# ui_cpu_power.net
KiCad netlist of a schematic drawn in Altium Designer
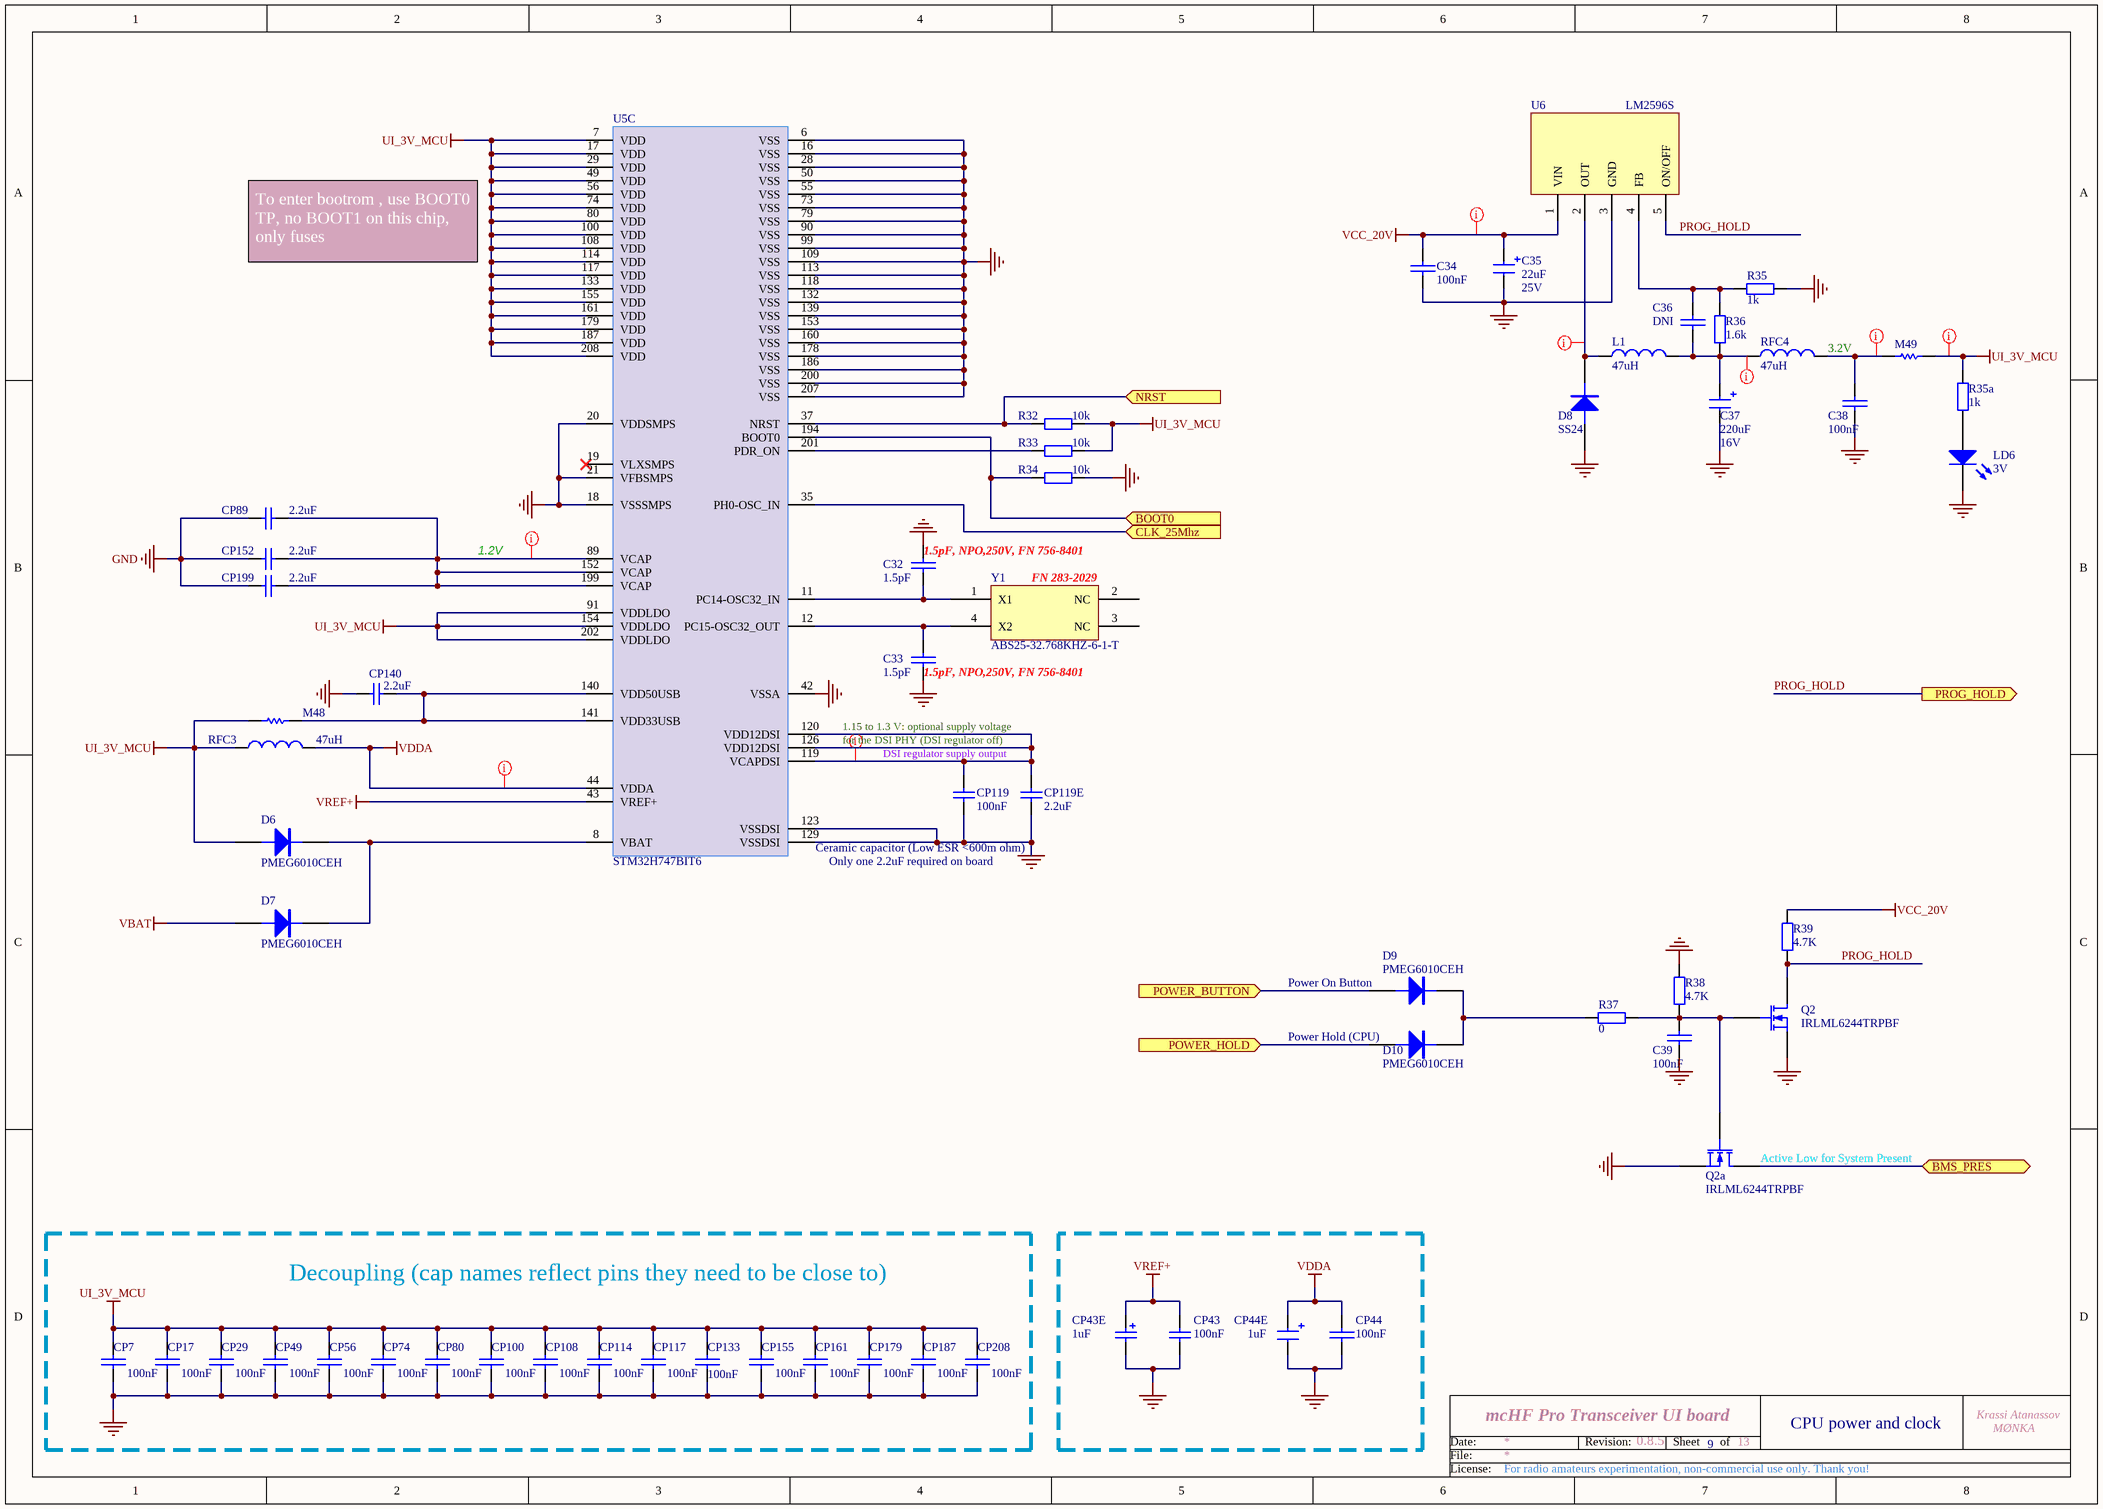
[diagram p0: ui_cpu_power.SchDoc]

(export (version "E")
  (design (tool "Eeschema 10.0.6"))
  (components
    (comp (ref "C32")
      (value "1.5pF")
      (footprint "0805")
      (description "Capacitor")
      (libsource (lib "mcHF_ui") (part "CAP"))
    )
    (comp (ref "C33")
      (value "1.5pF")
      (footprint "0805")
      (description "Capacitor")
      (libsource (lib "mcHF_ui") (part "CAP"))
    )
    (comp (ref "C34")
      (value "100nF")
      (footprint "0805")
      (description "Capacitor")
      (fields (field (name "VOLTAGE") "100V"))
      (libsource (lib "mcHF_rf") (part "CAP"))
    )
    (comp (ref "C35")
      (value "22uF")
      (footprint "1206_Elec_Cap")
      (description "Electrolitic capacitor")
      (fields (field (name "VOLTAGE") "25V"))
      (libsource (lib "mcHF_rf") (part "CAP-POL"))
    )
    (comp (ref "C36")
      (value "DNI")
      (footprint "0805")
      (description "Capacitor")
      (fields (field (name "VOLTAGE") "100V"))
      (libsource (lib "mcHF_rf") (part "CAP"))
    )
    (comp (ref "C37")
      (value "220uF")
      (footprint "CAP_ALUM_Pro")
      (description "Electrolitic capacitor")
      (fields (field (name "VOLTAGE") "16V"))
      (libsource (lib "mcHF_rf") (part "CAP-POL"))
    )
    (comp (ref "C38")
      (value "100nF")
      (footprint "0805")
      (description "Capacitor")
      (fields (field (name "VOLTAGE") "100V"))
      (libsource (lib "mcHF_rf") (part "CAP"))
    )
    (comp (ref "C39")
      (value "100nF")
      (footprint "0805")
      (description "Capacitor")
      (fields (field (name "VOLTAGE") "100V"))
      (libsource (lib "mcHF_rf") (part "CAP"))
    )
    (comp (ref "CP7")
      (value "100nF")
      (footprint "0805")
      (description "Capacitor")
      (libsource (lib "mcHF_ui") (part "CAP"))
    )
    (comp (ref "CP17")
      (value "100nF")
      (footprint "0805")
      (description "Capacitor")
      (libsource (lib "mcHF_ui") (part "CAP"))
    )
    (comp (ref "CP29")
      (value "100nF")
      (footprint "0805")
      (description "Capacitor")
      (libsource (lib "mcHF_ui") (part "CAP"))
    )
    (comp (ref "CP43")
      (value "100nF")
      (footprint "0805")
      (description "Capacitor")
      (fields (field (name "PUBLISHER") "Altium Limited"))
      (libsource (lib "Miscellaneous Devices") (part "Cap"))
    )
    (comp (ref "CP43E")
      (value "1uF")
      (footprint "1206_Elec_Cap")
      (fields (field (name "PUBLISHER") "Altium Limited"))
      (libsource (lib "Miscellaneous Devices") (part "Cap Pol1"))
    )
    (comp (ref "CP44")
      (value "100nF")
      (footprint "0805")
      (description "Capacitor")
      (libsource (lib "mcHF_ui") (part "CAP"))
    )
    (comp (ref "CP44E")
      (value "1uF")
      (footprint "1206_Elec_Cap")
      (description "Electrolitic capacitor")
      (libsource (lib "mcHF_ui") (part "CAP-POL"))
    )
    (comp (ref "CP49")
      (value "100nF")
      (footprint "0805")
      (description "Capacitor")
      (libsource (lib "mcHF_ui") (part "CAP"))
    )
    (comp (ref "CP56")
      (value "100nF")
      (footprint "0805")
      (description "Capacitor")
      (libsource (lib "mcHF_ui") (part "CAP"))
    )
    (comp (ref "CP74")
      (value "100nF")
      (footprint "0805")
      (description "Capacitor")
      (libsource (lib "mcHF_ui") (part "CAP"))
    )
    (comp (ref "CP80")
      (value "100nF")
      (footprint "0805")
      (description "Capacitor")
      (libsource (lib "mcHF_ui") (part "CAP"))
    )
    (comp (ref "CP89")
      (value "2.2uF")
      (footprint "0805")
      (description "Capacitor")
      (fields (field (name "PUBLISHER") "Altium Limited"))
      (libsource (lib "Miscellaneous Devices") (part "cap"))
    )
    (comp (ref "CP100")
      (value "100nF")
      (footprint "0805")
      (description "Capacitor")
      (libsource (lib "mcHF_ui") (part "CAP"))
    )
    (comp (ref "CP108")
      (value "100nF")
      (footprint "0805")
      (description "Capacitor")
      (libsource (lib "mcHF_ui") (part "CAP"))
    )
    (comp (ref "CP114")
      (value "100nF")
      (footprint "0805")
      (description "Capacitor")
      (libsource (lib "mcHF_ui") (part "CAP"))
    )
    (comp (ref "CP117")
      (value "100nF")
      (footprint "0805")
      (description "Capacitor")
      (libsource (lib "mcHF_ui") (part "CAP"))
    )
    (comp (ref "CP119")
      (value "100nF")
      (footprint "0805")
      (description "Capacitor")
      (fields (field (name "PUBLISHER") "Altium Limited"))
      (libsource (lib "Miscellaneous Devices") (part "CAP"))
    )
    (comp (ref "CP119E")
      (value "2.2uF")
      (footprint "0805")
      (description "Capacitor")
      (fields (field (name "PUBLISHER") "Altium Limited"))
      (libsource (lib "Miscellaneous Devices") (part "CAP"))
    )
    (comp (ref "CP133")
      (value "100nF")
      (footprint "0805")
      (description "Capacitor")
      (libsource (lib "mcHF_ui") (part "CAP"))
    )
    (comp (ref "CP140")
      (value "2.2uF")
      (footprint "0805")
      (description "0603  X5R 1礔")
      (fields (field (name "TOLERANCE") "10%"))
      (libsource (lib "MB963_1") (part "CAP SMD 0603  X5R 1礔 25V 10%"))
    )
    (comp (ref "CP152")
      (value "2.2uF")
      (footprint "0805")
      (description "Capacitor")
      (fields (field (name "PUBLISHER") "Altium Limited"))
      (libsource (lib "Miscellaneous Devices") (part "cap"))
    )
    (comp (ref "CP155")
      (value "100nF")
      (footprint "0805")
      (description "Capacitor")
      (libsource (lib "mcHF_ui") (part "CAP"))
    )
    (comp (ref "CP161")
      (value "100nF")
      (footprint "0805")
      (description "Capacitor")
      (libsource (lib "mcHF_ui") (part "CAP"))
    )
    (comp (ref "CP179")
      (value "100nF")
      (footprint "0805")
      (description "Capacitor")
      (libsource (lib "mcHF_ui") (part "CAP"))
    )
    (comp (ref "CP187")
      (value "100nF")
      (footprint "0805")
      (description "Capacitor")
      (libsource (lib "mcHF_ui") (part "CAP"))
    )
    (comp (ref "CP199")
      (value "2.2uF")
      (footprint "0805")
      (description "Capacitor")
      (fields (field (name "PUBLISHER") "Altium Limited"))
      (libsource (lib "Miscellaneous Devices") (part "Cap"))
    )
    (comp (ref "CP208")
      (value "100nF")
      (footprint "0805")
      (description "Capacitor")
      (libsource (lib "mcHF_ui") (part "CAP"))
    )
    (comp (ref "D6")
      (value "PMEG6010CEH")
      (footprint "SOD87")
      (description "DIODE, SCHOTTKY, 1A, 60V, SOD-123F")
      (libsource (lib "mcHF_rf") (part "PMEG6010CEH"))
    )
    (comp (ref "D7")
      (value "PMEG6010CEH")
      (footprint "SOD87")
      (description "DIODE, SCHOTTKY, 1A, 60V, SOD-123F")
      (libsource (lib "mcHF_rf") (part "PMEG6010CEH"))
    )
    (comp (ref "D8")
      (value "SS24")
      (footprint "DO214")
      (description "DIODE, SCHOTTKY, 1A, 60V, SOD-123F")
      (libsource (lib "mcHF_rf") (part "PMEG6010CEH"))
    )
    (comp (ref "D9")
      (value "PMEG6010CEH")
      (footprint "SOD87")
      (description "DIODE, SCHOTTKY, 1A, 60V, SOD-123F")
      (libsource (lib "mcHF_rf") (part "PMEG6010CEH"))
    )
    (comp (ref "D10")
      (value "PMEG6010CEH")
      (footprint "SOD87")
      (description "DIODE, SCHOTTKY, 1A, 60V, SOD-123F")
      (libsource (lib "mcHF_rf") (part "PMEG6010CEH"))
    )
    (comp (ref "L1")
      (value "47uH")
      (footprint "CD75")
      (description "POWER INDUCTOR, 47UH, 1210")
      (libsource (lib "mcHF_rf") (part "TDK-NLV25T"))
    )
    (comp (ref "LD6")
      (value "3V")
      (footprint "1206_Elec_Cap")
      (description "LED 3mm")
      (libsource (lib "mcHF_ui") (part "LED2"))
    )
    (comp (ref "M48")
      (value "0")
      (footprint "SB_0603")
      (description "Link")
      (fields (field (name "PUBLISHER") "Altium Limited"))
      (libsource (lib "__ui") (part "Link"))
    )
    (comp (ref "M49")
      (value "0")
      (footprint "SB_0603")
      (description "Link")
      (fields (field (name "PUBLISHER") "Altium Limited"))
      (libsource (lib "__ui") (part "Link"))
    )
    (comp (ref "Q2")
      (value "IRLML6244TRPBF")
      (footprint "SOT-23-Pro")
      (description "N-Channel MOSFET")
      (libsource (lib "mcHF_ui_b") (part "MOSFET-N"))
    )
    (comp (ref "Q2a")
      (value "IRLML6244TRPBF")
      (footprint "SOT-23-Pro")
      (description "N-Channel MOSFET")
      (libsource (lib "mcHF_ui_b") (part "MOSFET-N"))
    )
    (comp (ref "R32")
      (value "10k")
      (footprint "0805")
      (description "Resistor")
      (libsource (lib "mcHF_ui_b") (part "RES"))
    )
    (comp (ref "R33")
      (value "10k")
      (footprint "0805")
      (description "Resistor")
      (libsource (lib "mcHF_ui_b") (part "RES"))
    )
    (comp (ref "R34")
      (value "10k")
      (footprint "0805")
      (description "Resistor")
      (libsource (lib "mcHF_ui_b") (part "RES"))
    )
    (comp (ref "R35")
      (value "1k")
      (footprint "0805")
      (description "Resistor")
      (libsource (lib "mcHF_rf") (part "RES"))
    )
    (comp (ref "R35a")
      (value "1k")
      (footprint "0805")
      (description "Resistor")
      (libsource (lib "") (part "RES_1"))
    )
    (comp (ref "R36")
      (value "1.6k")
      (footprint "0805")
      (description "Resistor")
      (libsource (lib "") (part "RES_1"))
    )
    (comp (ref "R37")
      (value "0")
      (footprint "0805")
      (description "Resistor")
      (libsource (lib "mcHF_rf") (part "RES"))
    )
    (comp (ref "R38")
      (value "4.7K")
      (footprint "0805")
      (description "Resistor")
      (libsource (lib "") (part "RES_1"))
    )
    (comp (ref "R39")
      (value "4.7K")
      (footprint "0805")
      (description "Resistor")
      (libsource (lib "") (part "RES_1"))
    )
    (comp (ref "RFC3")
      (value "47uH")
      (footprint "0805")
      (description "Inductor")
      (fields (field (name "PUBLISHER") "Altium Limited"))
      (libsource (lib "Miscellaneous Devices") (part "Inductor"))
    )
    (comp (ref "RFC4")
      (value "47uH")
      (footprint "CD75")
      (description "POWER INDUCTOR, 47UH, 1210")
      (libsource (lib "mcHF_rf") (part "TDK-NLV25T"))
    )
    (comp (ref "U5")
      (value "STM32H747BIT6")
      (footprint "LQFP208-28x28x1.4")
      (description "STM32H747BIT6 LQFP208")
      (libsource (lib "__ui") (part "STM32H747BIT6"))
    )
    (comp (ref "U6")
      (value "LM2596S")
      (footprint "TO-263-5")
      (description "V REG ADJ +5/20V, SMPS TO-263-5")
      (libsource (lib "mcHF_rf") (part "LM2596S"))
    )
    (comp (ref "Y1")
      (value "ABS25-32.768KHZ-6-1-T")
      (footprint "__ui:DSO-N4")
      (description "32kHz Crystal")
      (libsource (lib "mcHF_ui_b") (part "SmdCrystal"))
    )
  )
  (nets
    (net (code "1") (name "/BMS_PRES") (class "Default")
      (node (ref "Q2a") (pin "3") (pinfunction "D_3") (pintype "passive"))
    )
    (net (code "2") (name "/BOOT0") (class "Default")
      (node (ref "R34") (pin "2") (pinfunction "2_2") (pintype "passive"))
      (node (ref "U5") (pin "194") (pinfunction "BOOT0_194") (pintype "passive"))
    )
    (net (code "3") (name "/CLK_25Mhz") (class "Default")
      (node (ref "U5") (pin "35") (pinfunction "PH0-OSC_IN_35") (pintype "passive"))
    )
    (net (code "4") (name "/NRST") (class "Default")
      (node (ref "R32") (pin "2") (pinfunction "2_2") (pintype "passive"))
      (node (ref "U5") (pin "37") (pinfunction "NRST_37") (pintype "passive"))
    )
    (net (code "5") (name "/POWER_BUTTON") (class "Default")
      (node (ref "D9") (pin "1") (pinfunction "A_1") (pintype "passive"))
    )
    (net (code "6") (name "/POWER_HOLD") (class "Default")
      (node (ref "D10") (pin "1") (pinfunction "A_1") (pintype "passive"))
    )
    (net (code "7") (name "/PROG_HOLD") (class "Default")
      (node (ref "Q2") (pin "3") (pinfunction "D_3") (pintype "passive"))
      (node (ref "R39") (pin "1") (pinfunction "1_1") (pintype "passive"))
      (node (ref "U6") (pin "5") (pinfunction "ON/OFF_5") (pintype "passive"))
    )
    (net (code "8") (name "GND") (class "Default")
      (node (ref "C32") (pin "2") (pinfunction "2_2") (pintype "passive"))
      (node (ref "C33") (pin "1") (pinfunction "1_1") (pintype "passive"))
      (node (ref "C34") (pin "2") (pinfunction "2_2") (pintype "passive"))
      (node (ref "C35") (pin "2") (pinfunction "2_2") (pintype "passive"))
      (node (ref "C37") (pin "2") (pinfunction "2_2") (pintype "passive"))
      (node (ref "C38") (pin "2") (pinfunction "2_2") (pintype "passive"))
      (node (ref "C39") (pin "2") (pinfunction "2_2") (pintype "passive"))
      (node (ref "CP100") (pin "2") (pinfunction "2_2") (pintype "passive"))
      (node (ref "CP108") (pin "2") (pinfunction "2_2") (pintype "passive"))
      (node (ref "CP114") (pin "2") (pinfunction "2_2") (pintype "passive"))
      (node (ref "CP117") (pin "2") (pinfunction "2_2") (pintype "passive"))
      (node (ref "CP119") (pin "2") (pinfunction "2_2") (pintype "passive"))
      (node (ref "CP119E") (pin "2") (pinfunction "2_2") (pintype "passive"))
      (node (ref "CP133") (pin "2") (pinfunction "2_2") (pintype "passive"))
      (node (ref "CP140") (pin "2") (pinfunction "2_2") (pintype "passive"))
      (node (ref "CP152") (pin "1") (pinfunction "1_1") (pintype "passive"))
      (node (ref "CP155") (pin "2") (pinfunction "2_2") (pintype "passive"))
      (node (ref "CP161") (pin "2") (pinfunction "2_2") (pintype "passive"))
      (node (ref "CP17") (pin "2") (pinfunction "2_2") (pintype "passive"))
      (node (ref "CP179") (pin "2") (pinfunction "2_2") (pintype "passive"))
      (node (ref "CP187") (pin "2") (pinfunction "2_2") (pintype "passive"))
      (node (ref "CP199") (pin "1") (pinfunction "1_1") (pintype "passive"))
      (node (ref "CP208") (pin "2") (pinfunction "2_2") (pintype "passive"))
      (node (ref "CP29") (pin "2") (pinfunction "2_2") (pintype "passive"))
      (node (ref "CP43") (pin "1") (pinfunction "1_1") (pintype "passive"))
      (node (ref "CP43E") (pin "2") (pinfunction "2_2") (pintype "passive"))
      (node (ref "CP44") (pin "2") (pinfunction "2_2") (pintype "passive"))
      (node (ref "CP44E") (pin "2") (pinfunction "2_2") (pintype "passive"))
      (node (ref "CP49") (pin "2") (pinfunction "2_2") (pintype "passive"))
      (node (ref "CP56") (pin "2") (pinfunction "2_2") (pintype "passive"))
      (node (ref "CP7") (pin "2") (pinfunction "2_2") (pintype "passive"))
      (node (ref "CP74") (pin "2") (pinfunction "2_2") (pintype "passive"))
      (node (ref "CP80") (pin "2") (pinfunction "2_2") (pintype "passive"))
      (node (ref "CP89") (pin "1") (pinfunction "1_1") (pintype "passive"))
      (node (ref "D8") (pin "1") (pinfunction "A_1") (pintype "passive"))
      (node (ref "LD6") (pin "2") (pinfunction "K_2") (pintype "passive"))
      (node (ref "Q2") (pin "2") (pinfunction "S_2") (pintype "passive"))
      (node (ref "Q2a") (pin "2") (pinfunction "S_2") (pintype "passive"))
      (node (ref "R34") (pin "1") (pinfunction "1_1") (pintype "passive"))
      (node (ref "R35") (pin "2") (pinfunction "2_2") (pintype "passive"))
      (node (ref "R38") (pin "2") (pinfunction "2_2") (pintype "passive"))
      (node (ref "U5") (pin "109") (pinfunction "VSS_109") (pintype "passive"))
      (node (ref "U5") (pin "113") (pinfunction "VSS_113") (pintype "passive"))
      (node (ref "U5") (pin "118") (pinfunction "VSS_118") (pintype "passive"))
      (node (ref "U5") (pin "123") (pinfunction "VSSDSI_123") (pintype "passive"))
      (node (ref "U5") (pin "129") (pinfunction "VSSDSI_129") (pintype "passive"))
      (node (ref "U5") (pin "132") (pinfunction "VSS_132") (pintype "passive"))
      (node (ref "U5") (pin "139") (pinfunction "VSS_139") (pintype "passive"))
      (node (ref "U5") (pin "153") (pinfunction "VSS_153") (pintype "passive"))
      (node (ref "U5") (pin "16") (pinfunction "VSS_16") (pintype "passive"))
      (node (ref "U5") (pin "160") (pinfunction "VSS_160") (pintype "passive"))
      (node (ref "U5") (pin "178") (pinfunction "VSS_178") (pintype "passive"))
      (node (ref "U5") (pin "18") (pinfunction "VSSSMPS_18") (pintype "passive"))
      (node (ref "U5") (pin "186") (pinfunction "VSS_186") (pintype "passive"))
      (node (ref "U5") (pin "20") (pinfunction "VDDSMPS_20") (pintype "passive"))
      (node (ref "U5") (pin "200") (pinfunction "VSS_200") (pintype "passive"))
      (node (ref "U5") (pin "207") (pinfunction "VSS_207") (pintype "passive"))
      (node (ref "U5") (pin "21") (pinfunction "VFBSMPS_21") (pintype "passive"))
      (node (ref "U5") (pin "28") (pinfunction "VSS_28") (pintype "passive"))
      (node (ref "U5") (pin "42") (pinfunction "VSSA_42") (pintype "passive"))
      (node (ref "U5") (pin "50") (pinfunction "VSS_50") (pintype "passive"))
      (node (ref "U5") (pin "55") (pinfunction "VSS_55") (pintype "passive"))
      (node (ref "U5") (pin "6") (pinfunction "VSS_6") (pintype "passive"))
      (node (ref "U5") (pin "73") (pinfunction "VSS_73") (pintype "passive"))
      (node (ref "U5") (pin "79") (pinfunction "VSS_79") (pintype "passive"))
      (node (ref "U5") (pin "90") (pinfunction "VSS_90") (pintype "passive"))
      (node (ref "U5") (pin "99") (pinfunction "VSS_99") (pintype "passive"))
      (node (ref "U6") (pin "3") (pinfunction "GND_3") (pintype "passive"))
    )
    (net (code "9") (name "Net-(C36-Pad2)") (class "Default")
      (node (ref "C36") (pin "2") (pinfunction "2_2") (pintype "passive"))
      (node (ref "C37") (pin "1") (pinfunction "1_1") (pintype "passive"))
      (node (ref "L1") (pin "2") (pinfunction "2_2") (pintype "passive"))
      (node (ref "R36") (pin "1") (pinfunction "1_1") (pintype "passive"))
      (node (ref "RFC4") (pin "1") (pinfunction "1_1") (pintype "passive"))
    )
    (net (code "10") (name "Net-(C38-Pad1)") (class "Default")
      (node (ref "C38") (pin "1") (pinfunction "1_1") (pintype "passive"))
      (node (ref "M49") (pin "1") (pinfunction "1_1") (pintype "passive"))
      (node (ref "RFC4") (pin "2") (pinfunction "2_2") (pintype "passive"))
    )
    (net (code "11") (name "Net-(CP152-Pad2)") (class "Default")
      (node (ref "CP152") (pin "2") (pinfunction "2_2") (pintype "passive"))
      (node (ref "CP199") (pin "2") (pinfunction "2_2") (pintype "passive"))
      (node (ref "CP89") (pin "2") (pinfunction "2_2") (pintype "passive"))
      (node (ref "U5") (pin "152") (pinfunction "VCAP_152") (pintype "passive"))
      (node (ref "U5") (pin "199") (pinfunction "VCAP_199") (pintype "passive"))
      (node (ref "U5") (pin "89") (pinfunction "VCAP_89") (pintype "passive"))
    )
    (net (code "12") (name "Net-(D6-K)") (class "Default")
      (node (ref "D6") (pin "2") (pinfunction "K_2") (pintype "passive"))
      (node (ref "D7") (pin "2") (pinfunction "K_2") (pintype "passive"))
      (node (ref "U5") (pin "8") (pinfunction "VBAT_8") (pintype "passive"))
    )
    (net (code "13") (name "Net-(D8-K)") (class "Default")
      (node (ref "D8") (pin "2") (pinfunction "K_2") (pintype "passive"))
      (node (ref "L1") (pin "1") (pinfunction "1_1") (pintype "passive"))
      (node (ref "U6") (pin "2") (pinfunction "OUT_2") (pintype "passive"))
    )
    (net (code "14") (name "Net-(D10-K)") (class "Default")
      (node (ref "D10") (pin "2") (pinfunction "K_2") (pintype "passive"))
      (node (ref "D9") (pin "2") (pinfunction "K_2") (pintype "passive"))
      (node (ref "R37") (pin "1") (pinfunction "1_1") (pintype "passive"))
    )
    (net (code "15") (name "Net-(LD6-A)") (class "Default")
      (node (ref "LD6") (pin "1") (pinfunction "A_1") (pintype "passive"))
      (node (ref "R35a") (pin "1") (pinfunction "1_1") (pintype "passive"))
    )
    (net (code "16") (name "Net-(Q2-G)") (class "Default")
      (node (ref "C39") (pin "1") (pinfunction "1_1") (pintype "passive"))
      (node (ref "Q2") (pin "1") (pinfunction "G_1") (pintype "passive"))
      (node (ref "Q2a") (pin "1") (pinfunction "G_1") (pintype "passive"))
      (node (ref "R37") (pin "2") (pinfunction "2_2") (pintype "passive"))
      (node (ref "R38") (pin "1") (pinfunction "1_1") (pintype "passive"))
    )
    (net (code "17") (name "Net-(U5C-PC14-OSC32_IN)") (class "Default")
      (node (ref "C32") (pin "1") (pinfunction "1_1") (pintype "passive"))
      (node (ref "U5") (pin "11") (pinfunction "PC14-OSC32_IN_11") (pintype "passive"))
      (node (ref "Y1") (pin "1") (pinfunction "X1_1") (pintype "passive"))
    )
    (net (code "18") (name "Net-(U5C-PC15-OSC32_OUT)") (class "Default")
      (node (ref "C33") (pin "2") (pinfunction "2_2") (pintype "passive"))
      (node (ref "U5") (pin "12") (pinfunction "PC15-OSC32_OUT_12") (pintype "passive"))
      (node (ref "Y1") (pin "4") (pinfunction "X2_4") (pintype "passive"))
    )
    (net (code "19") (name "Net-(U5C-PDR_ON)") (class "Default")
      (node (ref "R33") (pin "2") (pinfunction "2_2") (pintype "passive"))
      (node (ref "U5") (pin "201") (pinfunction "PDR_ON_201") (pintype "passive"))
    )
    (net (code "20") (name "Net-(U5C-VCAPDSI)") (class "Default")
      (node (ref "CP119") (pin "1") (pinfunction "1_1") (pintype "passive"))
      (node (ref "CP119E") (pin "1") (pinfunction "1_1") (pintype "passive"))
      (node (ref "U5") (pin "119") (pinfunction "VCAPDSI_119") (pintype "passive"))
      (node (ref "U5") (pin "120") (pinfunction "VDD12DSI_120") (pintype "passive"))
      (node (ref "U5") (pin "126") (pinfunction "VDD12DSI_126") (pintype "passive"))
    )
    (net (code "21") (name "Net-(U5C-VDD33USB)") (class "Default")
      (node (ref "CP140") (pin "1") (pinfunction "1_1") (pintype "passive"))
      (node (ref "M48") (pin "2") (pinfunction "2_2") (pintype "passive"))
      (node (ref "U5") (pin "140") (pinfunction "VDD50USB_140") (pintype "passive"))
      (node (ref "U5") (pin "141") (pinfunction "VDD33USB_141") (pintype "passive"))
    )
    (net (code "22") (name "Net-(U6-FB)") (class "Default")
      (node (ref "C36") (pin "1") (pinfunction "1_1") (pintype "passive"))
      (node (ref "R35") (pin "1") (pinfunction "1_1") (pintype "passive"))
      (node (ref "R36") (pin "2") (pinfunction "2_2") (pintype "passive"))
      (node (ref "U6") (pin "4") (pinfunction "FB_4") (pintype "passive"))
    )
    (net (code "23") (name "UI_3V_MCU") (class "Default")
      (node (ref "CP100") (pin "1") (pinfunction "1_1") (pintype "passive"))
      (node (ref "CP108") (pin "1") (pinfunction "1_1") (pintype "passive"))
      (node (ref "CP114") (pin "1") (pinfunction "1_1") (pintype "passive"))
      (node (ref "CP117") (pin "1") (pinfunction "1_1") (pintype "passive"))
      (node (ref "CP133") (pin "1") (pinfunction "1_1") (pintype "passive"))
      (node (ref "CP155") (pin "1") (pinfunction "1_1") (pintype "passive"))
      (node (ref "CP161") (pin "1") (pinfunction "1_1") (pintype "passive"))
      (node (ref "CP17") (pin "1") (pinfunction "1_1") (pintype "passive"))
      (node (ref "CP179") (pin "1") (pinfunction "1_1") (pintype "passive"))
      (node (ref "CP187") (pin "1") (pinfunction "1_1") (pintype "passive"))
      (node (ref "CP208") (pin "1") (pinfunction "1_1") (pintype "passive"))
      (node (ref "CP29") (pin "1") (pinfunction "1_1") (pintype "passive"))
      (node (ref "CP49") (pin "1") (pinfunction "1_1") (pintype "passive"))
      (node (ref "CP56") (pin "1") (pinfunction "1_1") (pintype "passive"))
      (node (ref "CP7") (pin "1") (pinfunction "1_1") (pintype "passive"))
      (node (ref "CP74") (pin "1") (pinfunction "1_1") (pintype "passive"))
      (node (ref "CP80") (pin "1") (pinfunction "1_1") (pintype "passive"))
      (node (ref "D6") (pin "1") (pinfunction "A_1") (pintype "passive"))
      (node (ref "M48") (pin "1") (pinfunction "1_1") (pintype "passive"))
      (node (ref "M49") (pin "2") (pinfunction "2_2") (pintype "passive"))
      (node (ref "R32") (pin "1") (pinfunction "1_1") (pintype "passive"))
      (node (ref "R33") (pin "1") (pinfunction "1_1") (pintype "passive"))
      (node (ref "R35a") (pin "2") (pinfunction "2_2") (pintype "passive"))
      (node (ref "RFC3") (pin "1") (pinfunction "1_1") (pintype "passive"))
      (node (ref "U5") (pin "100") (pinfunction "VDD_100") (pintype "passive"))
      (node (ref "U5") (pin "108") (pinfunction "VDD_108") (pintype "passive"))
      (node (ref "U5") (pin "114") (pinfunction "VDD_114") (pintype "passive"))
      (node (ref "U5") (pin "117") (pinfunction "VDD_117") (pintype "passive"))
      (node (ref "U5") (pin "133") (pinfunction "VDD_133") (pintype "passive"))
      (node (ref "U5") (pin "154") (pinfunction "VDDLDO_154") (pintype "passive"))
      (node (ref "U5") (pin "155") (pinfunction "VDD_155") (pintype "passive"))
      (node (ref "U5") (pin "161") (pinfunction "VDD_161") (pintype "passive"))
      (node (ref "U5") (pin "17") (pinfunction "VDD_17") (pintype "passive"))
      (node (ref "U5") (pin "179") (pinfunction "VDD_179") (pintype "passive"))
      (node (ref "U5") (pin "187") (pinfunction "VDD_187") (pintype "passive"))
      (node (ref "U5") (pin "202") (pinfunction "VDDLDO_202") (pintype "passive"))
      (node (ref "U5") (pin "208") (pinfunction "VDD_208") (pintype "passive"))
      (node (ref "U5") (pin "29") (pinfunction "VDD_29") (pintype "passive"))
      (node (ref "U5") (pin "49") (pinfunction "VDD_49") (pintype "passive"))
      (node (ref "U5") (pin "56") (pinfunction "VDD_56") (pintype "passive"))
      (node (ref "U5") (pin "7") (pinfunction "VDD_7") (pintype "passive"))
      (node (ref "U5") (pin "74") (pinfunction "VDD_74") (pintype "passive"))
      (node (ref "U5") (pin "80") (pinfunction "VDD_80") (pintype "passive"))
      (node (ref "U5") (pin "91") (pinfunction "VDDLDO_91") (pintype "passive"))
    )
    (net (code "24") (name "VBAT") (class "Default")
      (node (ref "D7") (pin "1") (pinfunction "A_1") (pintype "passive"))
    )
    (net (code "25") (name "VCC_20V") (class "Default")
      (node (ref "C34") (pin "1") (pinfunction "1_1") (pintype "passive"))
      (node (ref "C35") (pin "1") (pinfunction "1_1") (pintype "passive"))
      (node (ref "R39") (pin "2") (pinfunction "2_2") (pintype "passive"))
      (node (ref "U6") (pin "1") (pinfunction "VIN_1") (pintype "passive"))
    )
    (net (code "26") (name "VDDA") (class "Default")
      (node (ref "CP44") (pin "1") (pinfunction "1_1") (pintype "passive"))
      (node (ref "CP44E") (pin "1") (pinfunction "1_1") (pintype "passive"))
      (node (ref "RFC3") (pin "2") (pinfunction "2_2") (pintype "passive"))
      (node (ref "U5") (pin "44") (pinfunction "VDDA_44") (pintype "passive"))
    )
    (net (code "27") (name "VREF+") (class "Default")
      (node (ref "CP43") (pin "2") (pinfunction "2_2") (pintype "passive"))
      (node (ref "CP43E") (pin "1") (pinfunction "1_1") (pintype "passive"))
      (node (ref "U5") (pin "43") (pinfunction "VREF+_43") (pintype "passive"))
    )
    (net (code "28") (name "unconnected-(U5C-VLXSMPS-Pad19)") (class "Default")
      (node (ref "U5") (pin "19") (pinfunction "VLXSMPS_19") (pintype "passive+no_connect"))
    )
    (net (code "29") (name "unconnected-(Y1-NC-Pad2)") (class "Default")
      (node (ref "Y1") (pin "2") (pinfunction "NC_2") (pintype "passive"))
    )
    (net (code "30") (name "unconnected-(Y1-NC-Pad3)") (class "Default")
      (node (ref "Y1") (pin "3") (pinfunction "NC_3") (pintype "passive"))
    )
  )
)
